# RadioMusic_F_Rev2.net
KiCad netlist of a schematic drawn in EAGLE
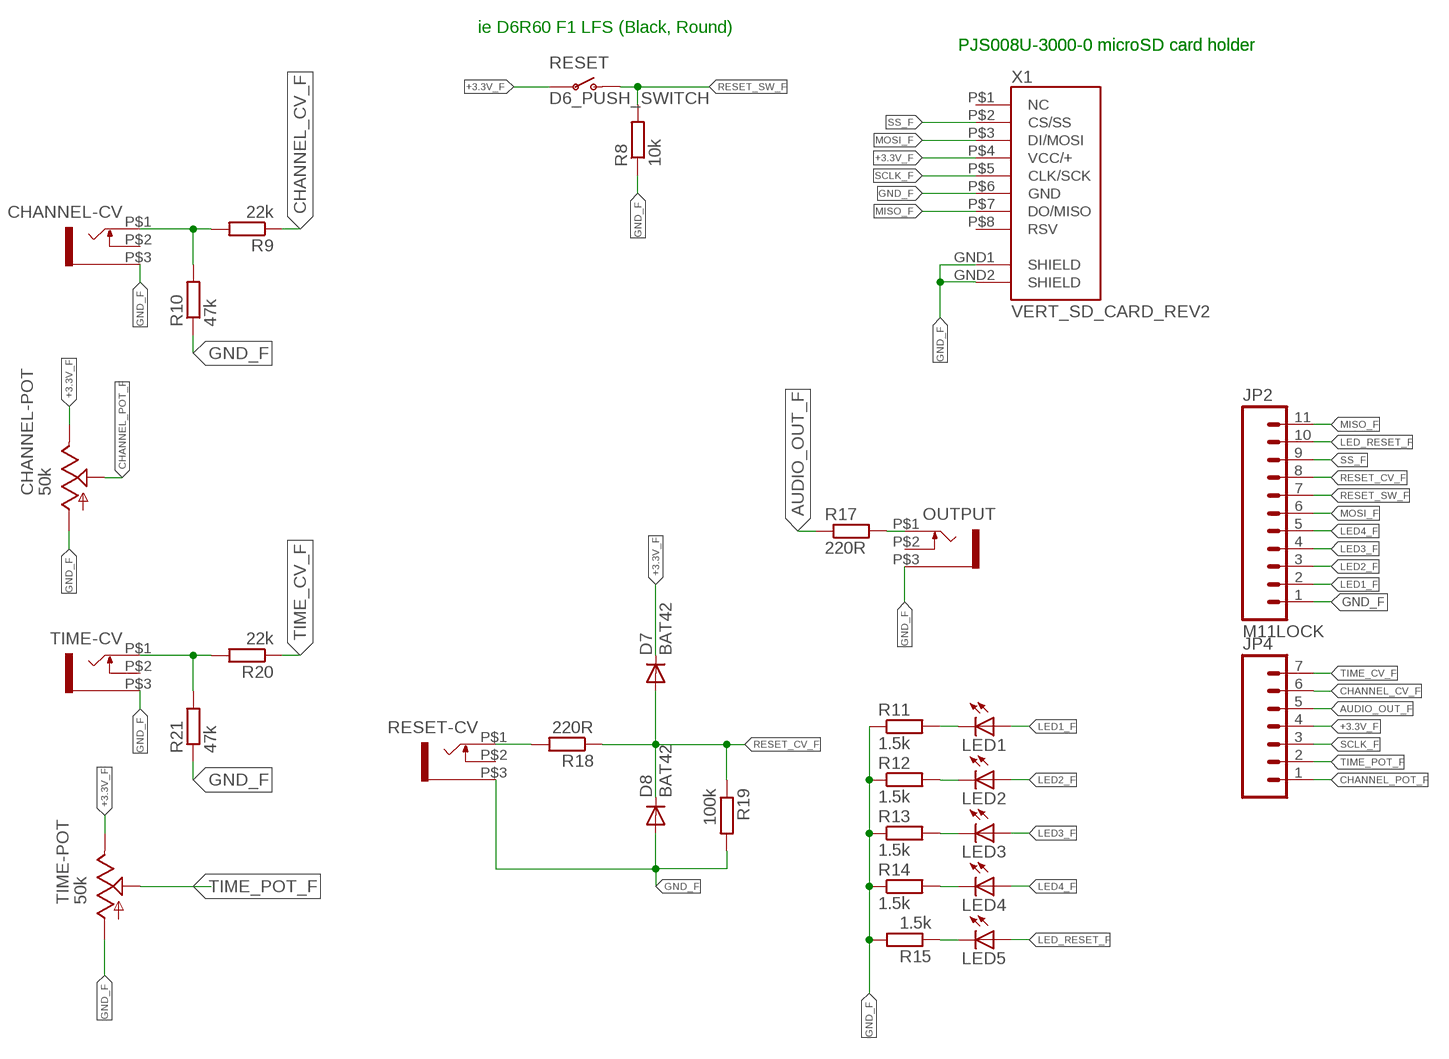
[diagram p0: schematic, sheet 1]

(export (version "E")
  (design (tool "Eeschema 10.0.6"))
  (components
    (comp (ref "CHANNEL-CV")
      (value "WQP-PJ301M-12_JACK")
      (footprint "eagle-import:WQP-PJ301M-12_JACK")
      (libsource (lib "eagle-import") (part "WQP-PJ301M-12_JACK"))
    )
    (comp (ref "CHANNEL-POT")
      (value "50k")
      (footprint "eagle-import:EVUF")
      (libsource (lib "eagle-import") (part "ALPHA-9MMAF2"))
    )
    (comp (ref "D7")
      (value "BAT42")
      (footprint "eagle-import:DO34-7")
      (libsource (lib "eagle-import") (part "BAT81"))
    )
    (comp (ref "D8")
      (value "BAT42")
      (footprint "eagle-import:DO34-7")
      (libsource (lib "eagle-import") (part "BAT81"))
    )
    (comp (ref "JP2")
      (value "M11LOCK")
      (footprint "eagle-import:1X11_LOCK")
      (libsource (lib "eagle-import") (part "M11LOCK"))
    )
    (comp (ref "JP4")
      (value "M07LOCK")
      (footprint "eagle-import:1X07_LOCK")
      (libsource (lib "eagle-import") (part "M07LOCK"))
    )
    (comp (ref "LED1")
      (value "LED3MM")
      (footprint "eagle-import:LED3MM")
      (libsource (lib "eagle-import") (part "LED3MM"))
    )
    (comp (ref "LED2")
      (value "LED3MM")
      (footprint "eagle-import:LED3MM")
      (libsource (lib "eagle-import") (part "LED3MM"))
    )
    (comp (ref "LED3")
      (value "LED3MM")
      (footprint "eagle-import:LED3MM")
      (libsource (lib "eagle-import") (part "LED3MM"))
    )
    (comp (ref "LED4")
      (value "LED3MM")
      (footprint "eagle-import:LED3MM")
      (libsource (lib "eagle-import") (part "LED3MM"))
    )
    (comp (ref "LED5")
      (value "LED3MM")
      (footprint "eagle-import:LED3MM")
      (libsource (lib "eagle-import") (part "LED3MM"))
    )
    (comp (ref "OUTPUT")
      (value "WQP-PJ301M-12_JACK")
      (footprint "eagle-import:WQP-PJ301M-12_JACK")
      (libsource (lib "eagle-import") (part "WQP-PJ301M-12_JACK"))
    )
    (comp (ref "R8")
      (value "10k")
      (footprint "eagle-import:0207_10")
      (libsource (lib "eagle-import") (part "R-EU_STANDARD_RESISTOR"))
    )
    (comp (ref "R9")
      (value "22k")
      (footprint "eagle-import:0207_10")
      (libsource (lib "eagle-import") (part "R-EU_STANDARD_RESISTOR"))
    )
    (comp (ref "R10")
      (value "47k")
      (footprint "eagle-import:0207_10")
      (libsource (lib "eagle-import") (part "R-EU_STANDARD_RESISTOR"))
    )
    (comp (ref "R11")
      (value "1.5k")
      (footprint "eagle-import:0207_10")
      (libsource (lib "eagle-import") (part "R-EU_STANDARD_RESISTOR"))
    )
    (comp (ref "R12")
      (value "1.5k")
      (footprint "eagle-import:0207_10")
      (libsource (lib "eagle-import") (part "R-EU_STANDARD_RESISTOR"))
    )
    (comp (ref "R13")
      (value "1.5k")
      (footprint "eagle-import:0207_10")
      (libsource (lib "eagle-import") (part "R-EU_STANDARD_RESISTOR"))
    )
    (comp (ref "R14")
      (value "1.5k")
      (footprint "eagle-import:0207_10")
      (libsource (lib "eagle-import") (part "R-EU_STANDARD_RESISTOR"))
    )
    (comp (ref "R15")
      (value "1.5k")
      (footprint "eagle-import:0207_10")
      (libsource (lib "eagle-import") (part "R-EU_STANDARD_RESISTOR"))
    )
    (comp (ref "R17")
      (value "220R")
      (footprint "eagle-import:0207_10")
      (libsource (lib "eagle-import") (part "R-EU_STANDARD_RESISTOR"))
    )
    (comp (ref "R18")
      (value "220R")
      (footprint "eagle-import:0207_10")
      (libsource (lib "eagle-import") (part "R-EU_STANDARD_RESISTOR"))
    )
    (comp (ref "R19")
      (value "100k")
      (footprint "eagle-import:0207_10")
      (libsource (lib "eagle-import") (part "R-EU_STANDARD_RESISTOR"))
    )
    (comp (ref "R20")
      (value "22k")
      (footprint "eagle-import:0207_10")
      (libsource (lib "eagle-import") (part "R-EU_STANDARD_RESISTOR"))
    )
    (comp (ref "R21")
      (value "47k")
      (footprint "eagle-import:0207_10")
      (libsource (lib "eagle-import") (part "R-EU_STANDARD_RESISTOR"))
    )
    (comp (ref "RESET")
      (value "D6_PUSH_SWITCH")
      (footprint "eagle-import:D6_BUTTON_RND")
      (libsource (lib "eagle-import") (part "D6_PUSH_SWITCH"))
    )
    (comp (ref "RESET-CV")
      (value "WQP-PJ301M-12_JACK")
      (footprint "eagle-import:WQP-PJ301M-12_JACK")
      (libsource (lib "eagle-import") (part "WQP-PJ301M-12_JACK"))
    )
    (comp (ref "TIME-CV")
      (value "WQP-PJ301M-12_JACK")
      (footprint "eagle-import:WQP-PJ301M-12_JACK")
      (libsource (lib "eagle-import") (part "WQP-PJ301M-12_JACK"))
    )
    (comp (ref "TIME-POT")
      (value "50k")
      (footprint "eagle-import:EVUF")
      (libsource (lib "eagle-import") (part "ALPHA-9MMAF2"))
    )
    (comp (ref "X1")
      (value "VERT_SD_CARD_REV2")
      (footprint "eagle-import:VERT_MICROSD_REV2")
      (libsource (lib "eagle-import") (part "VERT_SD_CARD_REV2"))
    )
  )
  (nets
    (net (code "1") (name "+3.3V_F") (class "Default")
      (node (ref "CHANNEL-POT") (pin "3") (pinfunction "E_3") (pintype "passive"))
      (node (ref "D7") (pin "C") (pinfunction "C_C") (pintype "passive"))
      (node (ref "JP4") (pin "4") (pinfunction "4_4") (pintype "passive"))
      (node (ref "RESET") (pin "P$3") (pinfunction "P_P$3") (pintype "passive"))
      (node (ref "RESET") (pin "P$4") (pinfunction "P_P$4") (pintype "passive"))
      (node (ref "TIME-POT") (pin "3") (pinfunction "E_3") (pintype "passive"))
      (node (ref "X1") (pin "P$4") (pinfunction "VCC/+_P$4") (pintype "bidirectional"))
    )
    (net (code "2") (name "AUDIO_OUT_F") (class "Default")
      (node (ref "JP4") (pin "5") (pinfunction "5_5") (pintype "passive"))
      (node (ref "R17") (pin "1") (pinfunction "1_1") (pintype "passive"))
    )
    (net (code "3") (name "CHANNEL_CV_F") (class "Default")
      (node (ref "JP4") (pin "6") (pinfunction "6_6") (pintype "passive"))
      (node (ref "R9") (pin "1") (pinfunction "1_1") (pintype "passive"))
    )
    (net (code "4") (name "CHANNEL_POT_F") (class "Default")
      (node (ref "CHANNEL-POT") (pin "2") (pinfunction "S_2") (pintype "passive"))
      (node (ref "JP4") (pin "1") (pinfunction "1_1") (pintype "passive"))
    )
    (net (code "5") (name "GND_F") (class "Default")
      (node (ref "CHANNEL-CV") (pin "P$3") (pinfunction "1_P$3") (pintype "passive"))
      (node (ref "CHANNEL-POT") (pin "1") (pinfunction "A_1") (pintype "passive"))
      (node (ref "D8") (pin "A") (pinfunction "A_A") (pintype "passive"))
      (node (ref "JP2") (pin "1") (pinfunction "1_1") (pintype "passive"))
      (node (ref "OUTPUT") (pin "P$3") (pinfunction "1_P$3") (pintype "passive"))
      (node (ref "R10") (pin "1") (pinfunction "1_1") (pintype "passive"))
      (node (ref "R11") (pin "1") (pinfunction "1_1") (pintype "passive"))
      (node (ref "R12") (pin "1") (pinfunction "1_1") (pintype "passive"))
      (node (ref "R13") (pin "1") (pinfunction "1_1") (pintype "passive"))
      (node (ref "R14") (pin "1") (pinfunction "1_1") (pintype "passive"))
      (node (ref "R15") (pin "2") (pinfunction "2_2") (pintype "passive"))
      (node (ref "R19") (pin "2") (pinfunction "2_2") (pintype "passive"))
      (node (ref "R21") (pin "1") (pinfunction "1_1") (pintype "passive"))
      (node (ref "R8") (pin "1") (pinfunction "1_1") (pintype "passive"))
      (node (ref "RESET-CV") (pin "P$3") (pinfunction "1_P$3") (pintype "passive"))
      (node (ref "TIME-CV") (pin "P$3") (pinfunction "1_P$3") (pintype "passive"))
      (node (ref "TIME-POT") (pin "1") (pinfunction "A_1") (pintype "passive"))
      (node (ref "X1") (pin "GND1") (pinfunction "SHIELD_GND1") (pintype "bidirectional"))
      (node (ref "X1") (pin "GND2") (pinfunction "SHIELD_GND2") (pintype "bidirectional"))
      (node (ref "X1") (pin "P$6") (pinfunction "GND_P$6") (pintype "bidirectional"))
    )
    (net (code "6") (name "LED1_F") (class "Default")
      (node (ref "JP2") (pin "2") (pinfunction "2_2") (pintype "passive"))
      (node (ref "LED1") (pin "A") (pinfunction "A_A") (pintype "passive"))
    )
    (net (code "7") (name "LED2_F") (class "Default")
      (node (ref "JP2") (pin "3") (pinfunction "3_3") (pintype "passive"))
      (node (ref "LED2") (pin "A") (pinfunction "A_A") (pintype "passive"))
    )
    (net (code "8") (name "LED3_F") (class "Default")
      (node (ref "JP2") (pin "4") (pinfunction "4_4") (pintype "passive"))
      (node (ref "LED3") (pin "A") (pinfunction "A_A") (pintype "passive"))
    )
    (net (code "9") (name "LED4_F") (class "Default")
      (node (ref "JP2") (pin "5") (pinfunction "5_5") (pintype "passive"))
      (node (ref "LED4") (pin "A") (pinfunction "A_A") (pintype "passive"))
    )
    (net (code "10") (name "LED_RESET_F") (class "Default")
      (node (ref "JP2") (pin "10") (pinfunction "10_10") (pintype "passive"))
      (node (ref "LED5") (pin "A") (pinfunction "A_A") (pintype "passive"))
    )
    (net (code "11") (name "MISO_F") (class "Default")
      (node (ref "JP2") (pin "11") (pinfunction "11_11") (pintype "passive"))
      (node (ref "X1") (pin "P$7") (pinfunction "DO/MISO_P$7") (pintype "bidirectional"))
    )
    (net (code "12") (name "MOSI_F") (class "Default")
      (node (ref "JP2") (pin "6") (pinfunction "6_6") (pintype "passive"))
      (node (ref "X1") (pin "P$3") (pinfunction "DI/MOSI_P$3") (pintype "bidirectional"))
    )
    (net (code "13") (name "Net-(CHANNEL-CV-2)") (class "Default")
      (node (ref "CHANNEL-CV") (pin "P$1") (pinfunction "2_P$1") (pintype "passive"))
      (node (ref "R10") (pin "2") (pinfunction "2_2") (pintype "passive"))
      (node (ref "R9") (pin "2") (pinfunction "2_2") (pintype "passive"))
    )
    (net (code "14") (name "Net-(LED1-C)") (class "Default")
      (node (ref "LED1") (pin "K") (pinfunction "C_K") (pintype "passive"))
      (node (ref "R11") (pin "2") (pinfunction "2_2") (pintype "passive"))
    )
    (net (code "15") (name "Net-(LED2-C)") (class "Default")
      (node (ref "LED2") (pin "K") (pinfunction "C_K") (pintype "passive"))
      (node (ref "R12") (pin "2") (pinfunction "2_2") (pintype "passive"))
    )
    (net (code "16") (name "Net-(LED3-C)") (class "Default")
      (node (ref "LED3") (pin "K") (pinfunction "C_K") (pintype "passive"))
      (node (ref "R13") (pin "2") (pinfunction "2_2") (pintype "passive"))
    )
    (net (code "17") (name "Net-(LED4-C)") (class "Default")
      (node (ref "LED4") (pin "K") (pinfunction "C_K") (pintype "passive"))
      (node (ref "R14") (pin "2") (pinfunction "2_2") (pintype "passive"))
    )
    (net (code "18") (name "Net-(LED5-C)") (class "Default")
      (node (ref "LED5") (pin "K") (pinfunction "C_K") (pintype "passive"))
      (node (ref "R15") (pin "1") (pinfunction "1_1") (pintype "passive"))
    )
    (net (code "19") (name "Net-(OUTPUT-2)") (class "Default")
      (node (ref "OUTPUT") (pin "P$1") (pinfunction "2_P$1") (pintype "passive"))
      (node (ref "R17") (pin "2") (pinfunction "2_2") (pintype "passive"))
    )
    (net (code "20") (name "Net-(RESET-CV-2)") (class "Default")
      (node (ref "R18") (pin "2") (pinfunction "2_2") (pintype "passive"))
      (node (ref "RESET-CV") (pin "P$1") (pinfunction "2_P$1") (pintype "passive"))
    )
    (net (code "21") (name "Net-(TIME-CV-2)") (class "Default")
      (node (ref "R20") (pin "2") (pinfunction "2_2") (pintype "passive"))
      (node (ref "R21") (pin "2") (pinfunction "2_2") (pintype "passive"))
      (node (ref "TIME-CV") (pin "P$1") (pinfunction "2_P$1") (pintype "passive"))
    )
    (net (code "22") (name "RESET_CV_F") (class "Default")
      (node (ref "D7") (pin "A") (pinfunction "A_A") (pintype "passive"))
      (node (ref "D8") (pin "C") (pinfunction "C_C") (pintype "passive"))
      (node (ref "JP2") (pin "8") (pinfunction "8_8") (pintype "passive"))
      (node (ref "R18") (pin "1") (pinfunction "1_1") (pintype "passive"))
      (node (ref "R19") (pin "1") (pinfunction "1_1") (pintype "passive"))
    )
    (net (code "23") (name "RESET_SW_F") (class "Default")
      (node (ref "JP2") (pin "7") (pinfunction "7_7") (pintype "passive"))
      (node (ref "R8") (pin "2") (pinfunction "2_2") (pintype "passive"))
      (node (ref "RESET") (pin "P$1") (pinfunction "O_P$1") (pintype "passive"))
      (node (ref "RESET") (pin "P$2") (pinfunction "O_P$2") (pintype "passive"))
    )
    (net (code "24") (name "SCLK_F") (class "Default")
      (node (ref "JP4") (pin "3") (pinfunction "3_3") (pintype "passive"))
      (node (ref "X1") (pin "P$5") (pinfunction "CLK/SCK_P$5") (pintype "bidirectional"))
    )
    (net (code "25") (name "SS_F") (class "Default")
      (node (ref "JP2") (pin "9") (pinfunction "9_9") (pintype "passive"))
      (node (ref "X1") (pin "P$2") (pinfunction "CS/SS_P$2") (pintype "bidirectional"))
    )
    (net (code "26") (name "TIME_CV_F") (class "Default")
      (node (ref "JP4") (pin "7") (pinfunction "7_7") (pintype "passive"))
      (node (ref "R20") (pin "1") (pinfunction "1_1") (pintype "passive"))
    )
    (net (code "27") (name "TIME_POT_F") (class "Default")
      (node (ref "JP4") (pin "2") (pinfunction "2_2") (pintype "passive"))
      (node (ref "TIME-POT") (pin "2") (pinfunction "S_2") (pintype "passive"))
    )
    (net (code "28") (name "unconnected-(CHANNEL-CV-3-PadP$2)") (class "Default")
      (node (ref "CHANNEL-CV") (pin "P$2") (pinfunction "3_P$2") (pintype "passive"))
    )
    (net (code "29") (name "unconnected-(OUTPUT-3-PadP$2)") (class "Default")
      (node (ref "OUTPUT") (pin "P$2") (pinfunction "3_P$2") (pintype "passive"))
    )
    (net (code "30") (name "unconnected-(RESET-CV-3-PadP$2)") (class "Default")
      (node (ref "RESET-CV") (pin "P$2") (pinfunction "3_P$2") (pintype "passive"))
    )
    (net (code "31") (name "unconnected-(TIME-CV-3-PadP$2)") (class "Default")
      (node (ref "TIME-CV") (pin "P$2") (pinfunction "3_P$2") (pintype "passive"))
    )
    (net (code "32") (name "unconnected-(X1-NC-PadP$1)") (class "Default")
      (node (ref "X1") (pin "P$1") (pinfunction "NC_P$1") (pintype "bidirectional"))
    )
    (net (code "33") (name "unconnected-(X1-RSV-PadP$8)") (class "Default")
      (node (ref "X1") (pin "P$8") (pinfunction "RSV_P$8") (pintype "bidirectional"))
    )
  )
)
